# phoneline_fixer_v2_0.net
KiCad netlist of a schematic drawn in EAGLE
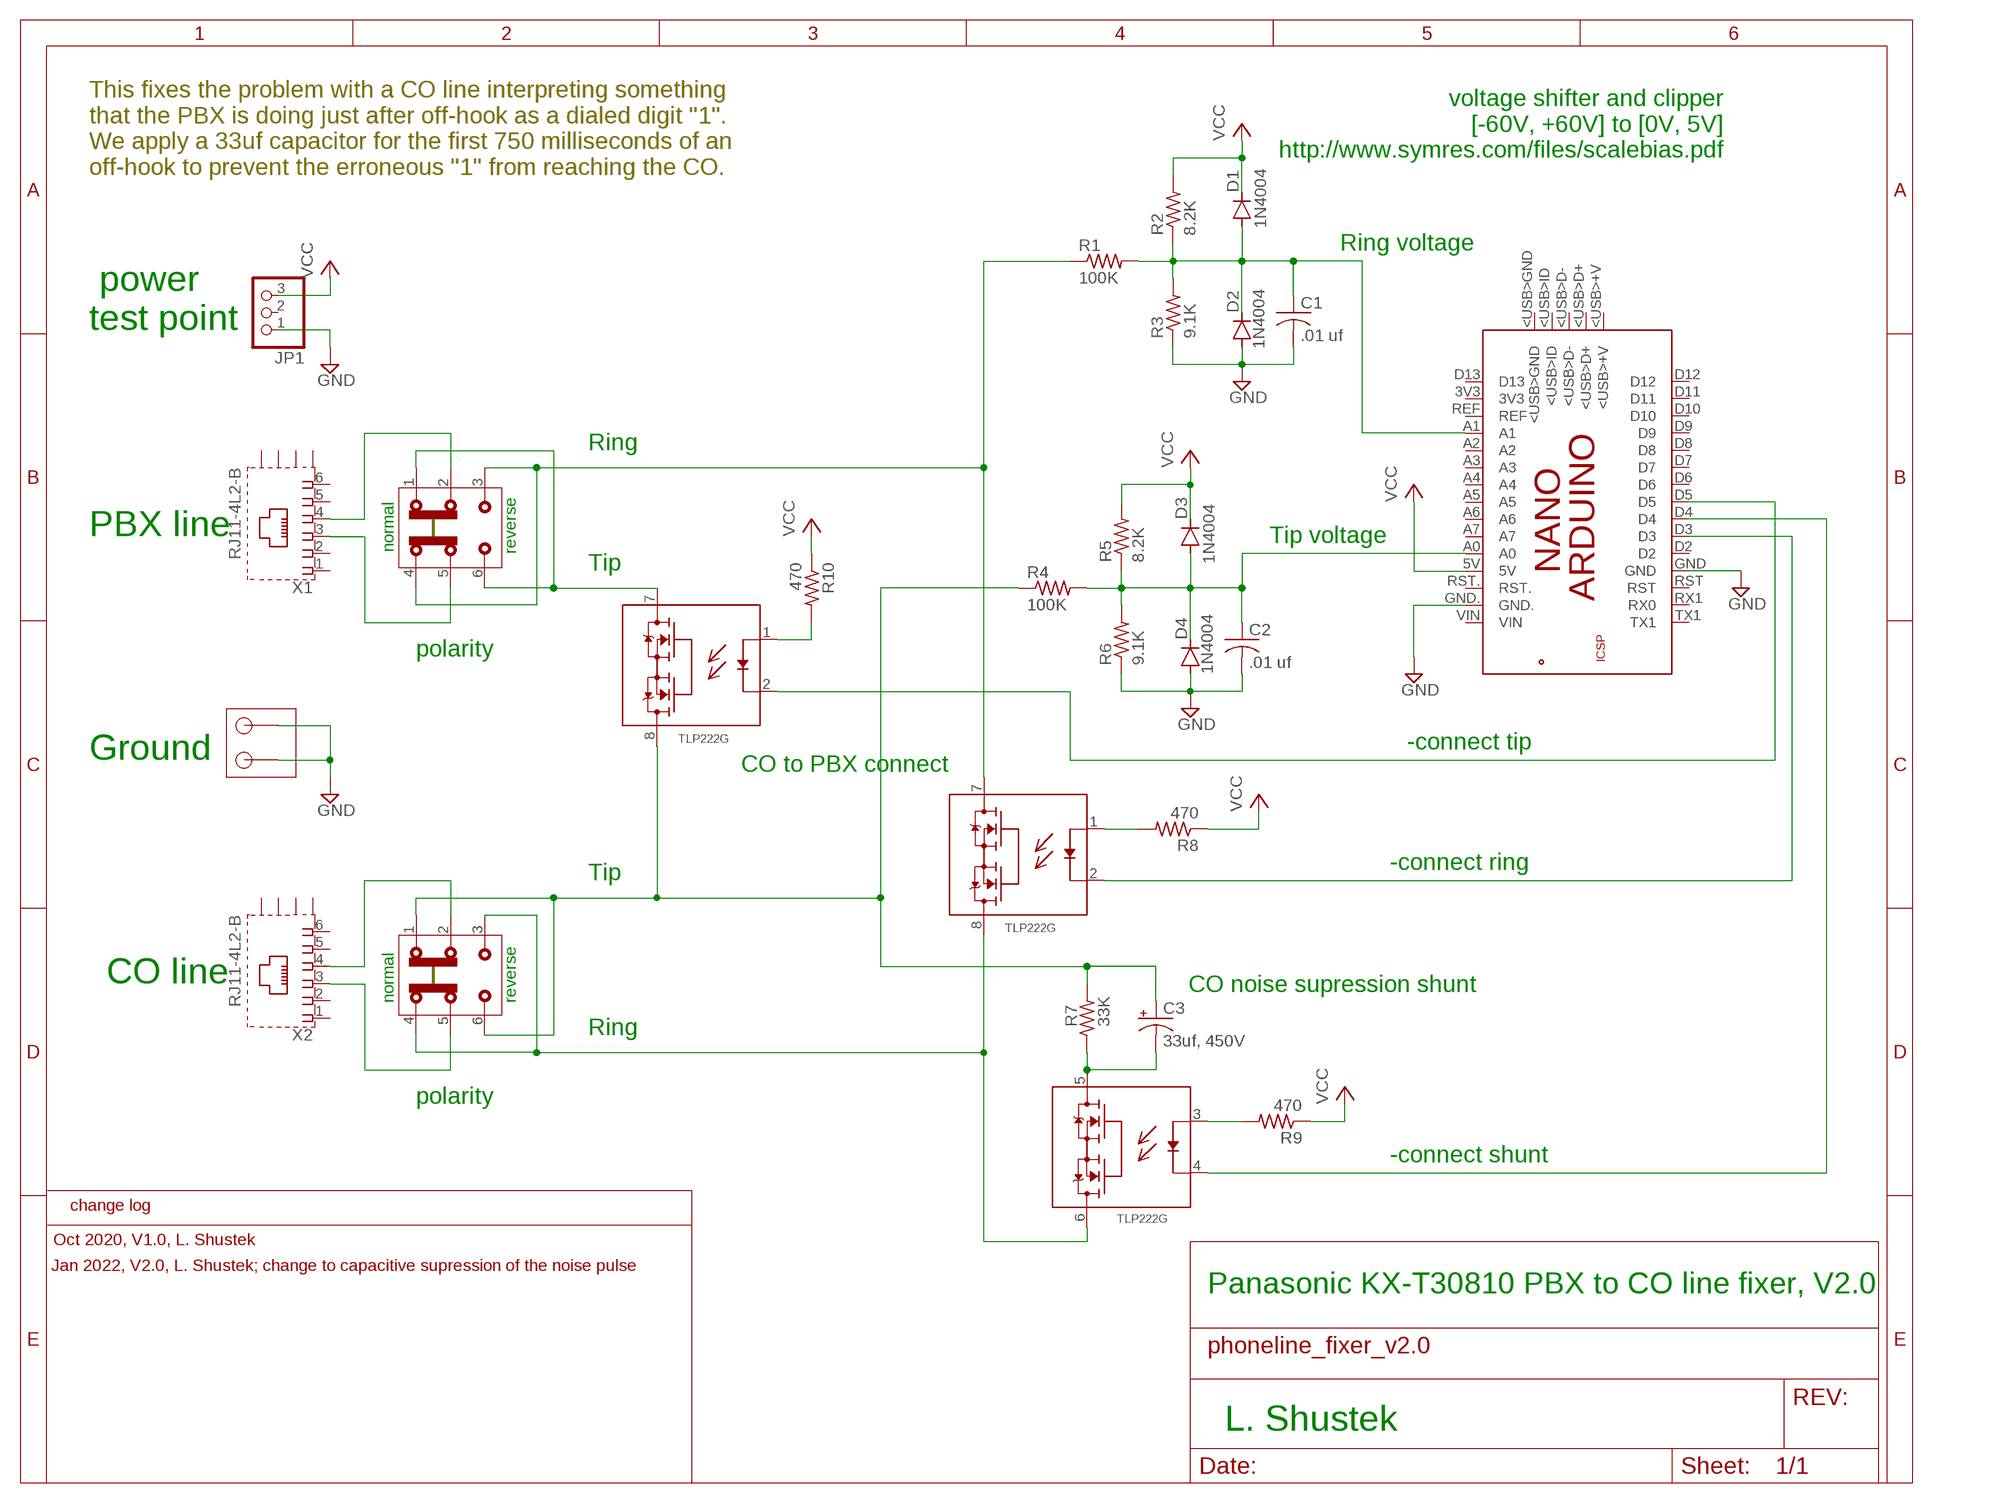
[diagram p0: schematic, sheet 1]

(export (version "E")
  (design (tool "Eeschema 10.0.6"))
  (components
    (comp (ref "C1")
      (value ".01 uf")
      (footprint "eagle-import:C050-025X075")
      (libsource (lib "eagle-import") (part "C-US050-025X075"))
    )
    (comp (ref "C2")
      (value ".01 uf")
      (footprint "eagle-import:C050-025X075")
      (libsource (lib "eagle-import") (part "C-US050-025X075"))
    )
    (comp (ref "C3")
      (value "33uf, 450V")
      (footprint "eagle-import:E7,5-18")
      (libsource (lib "eagle-import") (part "CPOL-USE7.5-18"))
    )
    (comp (ref "D1")
      (value "1N4004")
      (footprint "eagle-import:DO41-10")
      (libsource (lib "eagle-import") (part "1N4004"))
    )
    (comp (ref "D2")
      (value "1N4004")
      (footprint "eagle-import:DO41-10")
      (libsource (lib "eagle-import") (part "1N4004"))
    )
    (comp (ref "D3")
      (value "1N4004")
      (footprint "eagle-import:DO41-10")
      (libsource (lib "eagle-import") (part "1N4004"))
    )
    (comp (ref "D4")
      (value "1N4004")
      (footprint "eagle-import:DO41-10")
      (libsource (lib "eagle-import") (part "1N4004"))
    )
    (comp (ref "JP1")
      (value "PINHD-1X3")
      (footprint "eagle-import:1X03")
      (libsource (lib "eagle-import") (part "PINHD-1X3"))
    )
    (comp (ref "PCB1")
      (value "ARDUINO_NANO")
      (footprint "eagle-import:ARDUINO_NANO")
      (libsource (lib "eagle-import") (part "ARDUINO_NANO"))
    )
    (comp (ref "R1")
      (value "100K")
      (footprint "eagle-import:0207_12")
      (libsource (lib "eagle-import") (part "R-US_0207/12"))
    )
    (comp (ref "R2")
      (value "8.2K")
      (footprint "eagle-import:0207_12")
      (libsource (lib "eagle-import") (part "R-US_0207/12"))
    )
    (comp (ref "R3")
      (value "9.1K")
      (footprint "eagle-import:0207_12")
      (libsource (lib "eagle-import") (part "R-US_0207/12"))
    )
    (comp (ref "R4")
      (value "100K")
      (footprint "eagle-import:0207_12")
      (libsource (lib "eagle-import") (part "R-US_0207/12"))
    )
    (comp (ref "R5")
      (value "8.2K")
      (footprint "eagle-import:0207_12")
      (libsource (lib "eagle-import") (part "R-US_0207/12"))
    )
    (comp (ref "R6")
      (value "9.1K")
      (footprint "eagle-import:0207_12")
      (libsource (lib "eagle-import") (part "R-US_0207/12"))
    )
    (comp (ref "R7")
      (value "33K")
      (footprint "eagle-import:0414_15")
      (libsource (lib "eagle-import") (part "R-US_0414/15"))
    )
    (comp (ref "R8")
      (value "470")
      (footprint "eagle-import:0207_12")
      (libsource (lib "eagle-import") (part "R-US_0207/12"))
    )
    (comp (ref "R9")
      (value "470")
      (footprint "eagle-import:0207_12")
      (libsource (lib "eagle-import") (part "R-US_0207/12"))
    )
    (comp (ref "R10")
      (value "470")
      (footprint "eagle-import:0207_12")
      (libsource (lib "eagle-import") (part "R-US_0207/12"))
    )
    (comp (ref "U$1")
      (value "TLP222G")
      (footprint "eagle-import:DIL08")
      (libsource (lib "eagle-import") (part "PHOTORELAY"))
    )
    (comp (ref "U$2")
      (value "CONNECTOR-2PINTHIN")
      (footprint "eagle-import:CONNECTOR-2PIN-5MM_THIN")
      (libsource (lib "eagle-import") (part "CONNECTOR-2PINTHIN"))
    )
    (comp (ref "U$3")
      (value "SWITCH_SLIDE_DPDT")
      (footprint "eagle-import:SWITCH_SLIDE_DPDT")
      (libsource (lib "eagle-import") (part "SWITCH_SLIDE_DPDT"))
    )
    (comp (ref "U$4")
      (value "SWITCH_SLIDE_DPDT")
      (footprint "eagle-import:SWITCH_SLIDE_DPDT")
      (libsource (lib "eagle-import") (part "SWITCH_SLIDE_DPDT"))
    )
    (comp (ref "U$5")
      (value "TLP222G")
      (footprint "eagle-import:DIL08")
      (libsource (lib "eagle-import") (part "PHOTORELAY"))
    )
    (comp (ref "X1")
      (value "RJ11-4L2-B")
      (footprint "eagle-import:RJ11-SHIELD2")
      (fields (field (name "MF") "TYCO ELECTRONICS"))
      (libsource (lib "eagle-import") (part "RJ112-B-4L"))
    )
    (comp (ref "X2")
      (value "RJ11-4L2-B")
      (footprint "eagle-import:RJ11-SHIELD2")
      (fields (field (name "MF") "TYCO ELECTRONICS"))
      (libsource (lib "eagle-import") (part "RJ112-B-4L"))
    )
  )
  (nets
    (net (code "1") (name "GND") (class "Default")
      (node (ref "C1") (pin "2") (pinfunction "2_2") (pintype "passive"))
      (node (ref "C2") (pin "2") (pinfunction "2_2") (pintype "passive"))
      (node (ref "D2") (pin "A") (pinfunction "A_A") (pintype "passive"))
      (node (ref "D4") (pin "A") (pinfunction "A_A") (pintype "passive"))
      (node (ref "JP1") (pin "1") (pinfunction "1_1") (pintype "passive"))
      (node (ref "PCB1") (pin "GND") (pinfunction "GND_GND") (pintype "bidirectional"))
      (node (ref "PCB1") (pin "GND.") (pinfunction "GND._GND.") (pintype "bidirectional"))
      (node (ref "R3") (pin "1") (pinfunction "1_1") (pintype "passive"))
      (node (ref "R6") (pin "1") (pinfunction "1_1") (pintype "passive"))
      (node (ref "U$2") (pin "P$1") (pinfunction "P$1_P$1") (pintype "bidirectional"))
      (node (ref "U$2") (pin "P$2") (pinfunction "P$2_P$2") (pintype "bidirectional"))
    )
    (net (code "2") (name "Net-(C1-Pad1)") (class "Default")
      (node (ref "C1") (pin "1") (pinfunction "1_1") (pintype "passive"))
      (node (ref "D1") (pin "A") (pinfunction "A_A") (pintype "passive"))
      (node (ref "D2") (pin "C") (pinfunction "C_C") (pintype "passive"))
      (node (ref "PCB1") (pin "A1") (pinfunction "A1_A1") (pintype "bidirectional"))
      (node (ref "R1") (pin "2") (pinfunction "2_2") (pintype "passive"))
      (node (ref "R2") (pin "1") (pinfunction "1_1") (pintype "passive"))
      (node (ref "R3") (pin "2") (pinfunction "2_2") (pintype "passive"))
    )
    (net (code "3") (name "Net-(C2-Pad1)") (class "Default")
      (node (ref "C2") (pin "1") (pinfunction "1_1") (pintype "passive"))
      (node (ref "D3") (pin "A") (pinfunction "A_A") (pintype "passive"))
      (node (ref "D4") (pin "C") (pinfunction "C_C") (pintype "passive"))
      (node (ref "PCB1") (pin "A0") (pinfunction "A0_A0") (pintype "bidirectional"))
      (node (ref "R4") (pin "2") (pinfunction "2_2") (pintype "passive"))
      (node (ref "R5") (pin "1") (pinfunction "1_1") (pintype "passive"))
      (node (ref "R6") (pin "2") (pinfunction "2_2") (pintype "passive"))
    )
    (net (code "4") (name "Net-(U$1A-A)") (class "Default")
      (node (ref "R8") (pin "2") (pinfunction "2_2") (pintype "passive"))
      (node (ref "U$1") (pin "1") (pinfunction "A_1") (pintype "bidirectional"))
    )
    (net (code "5") (name "Net-(U$1A-C)") (class "Default")
      (node (ref "PCB1") (pin "D3") (pinfunction "D3_D3") (pintype "bidirectional"))
      (node (ref "U$1") (pin "2") (pinfunction "C_2") (pintype "bidirectional"))
    )
    (net (code "6") (name "Net-(U$1A-D1)") (class "Default")
      (node (ref "U$1") (pin "6") (pinfunction "D1_6") (pintype "bidirectional"))
      (node (ref "U$1") (pin "8") (pinfunction "D1_8") (pintype "bidirectional"))
      (node (ref "U$4") (pin "3") (pinfunction "3_3") (pintype "bidirectional"))
      (node (ref "U$4") (pin "4") (pinfunction "4_4") (pintype "bidirectional"))
    )
    (net (code "7") (name "Net-(U$1A-D2)") (class "Default")
      (node (ref "R1") (pin "1") (pinfunction "1_1") (pintype "passive"))
      (node (ref "U$1") (pin "7") (pinfunction "D2_7") (pintype "bidirectional"))
      (node (ref "U$3") (pin "3") (pinfunction "3_3") (pintype "bidirectional"))
      (node (ref "U$3") (pin "4") (pinfunction "4_4") (pintype "bidirectional"))
    )
    (net (code "8") (name "Net-(U$1B-A)") (class "Default")
      (node (ref "R9") (pin "2") (pinfunction "2_2") (pintype "passive"))
      (node (ref "U$1") (pin "3") (pinfunction "A_3") (pintype "bidirectional"))
    )
    (net (code "9") (name "Net-(U$1B-C)") (class "Default")
      (node (ref "PCB1") (pin "D4") (pinfunction "D4_D4") (pintype "bidirectional"))
      (node (ref "U$1") (pin "4") (pinfunction "C_4") (pintype "bidirectional"))
    )
    (net (code "10") (name "Net-(U$1B-D2)") (class "Default")
      (node (ref "C3") (pin "-") (pinfunction "-_-") (pintype "passive"))
      (node (ref "R7") (pin "1") (pinfunction "1_1") (pintype "passive"))
      (node (ref "U$1") (pin "5") (pinfunction "D2_5") (pintype "bidirectional"))
    )
    (net (code "11") (name "Net-(U$3-Pad2)") (class "Default")
      (node (ref "U$3") (pin "2") (pinfunction "2_2") (pintype "bidirectional"))
      (node (ref "X1") (pin "4") (pinfunction "4_4") (pintype "passive"))
    )
    (net (code "12") (name "Net-(U$3-Pad5)") (class "Default")
      (node (ref "U$3") (pin "5") (pinfunction "5_5") (pintype "bidirectional"))
      (node (ref "X1") (pin "3") (pinfunction "3_3") (pintype "passive"))
    )
    (net (code "13") (name "Net-(U$4-Pad2)") (class "Default")
      (node (ref "U$4") (pin "2") (pinfunction "2_2") (pintype "bidirectional"))
      (node (ref "X2") (pin "4") (pinfunction "4_4") (pintype "passive"))
    )
    (net (code "14") (name "Net-(U$4-Pad5)") (class "Default")
      (node (ref "U$4") (pin "5") (pinfunction "5_5") (pintype "bidirectional"))
      (node (ref "X2") (pin "3") (pinfunction "3_3") (pintype "passive"))
    )
    (net (code "15") (name "Net-(U$5A-A)") (class "Default")
      (node (ref "R10") (pin "2") (pinfunction "2_2") (pintype "passive"))
      (node (ref "U$5") (pin "1") (pinfunction "A_1") (pintype "bidirectional"))
    )
    (net (code "16") (name "Net-(U$5A-C)") (class "Default")
      (node (ref "PCB1") (pin "D5") (pinfunction "D5_D5") (pintype "bidirectional"))
      (node (ref "U$5") (pin "2") (pinfunction "C_2") (pintype "bidirectional"))
    )
    (net (code "17") (name "Net-(U$5A-D1)") (class "Default")
      (node (ref "C3") (pin "+") (pinfunction "+_+") (pintype "passive"))
      (node (ref "R4") (pin "1") (pinfunction "1_1") (pintype "passive"))
      (node (ref "R7") (pin "2") (pinfunction "2_2") (pintype "passive"))
      (node (ref "U$4") (pin "1") (pinfunction "1_1") (pintype "bidirectional"))
      (node (ref "U$4") (pin "6") (pinfunction "6_6") (pintype "bidirectional"))
      (node (ref "U$5") (pin "8") (pinfunction "D1_8") (pintype "bidirectional"))
    )
    (net (code "18") (name "Net-(U$5A-D2)") (class "Default")
      (node (ref "U$3") (pin "1") (pinfunction "1_1") (pintype "bidirectional"))
      (node (ref "U$3") (pin "6") (pinfunction "6_6") (pintype "bidirectional"))
      (node (ref "U$5") (pin "7") (pinfunction "D2_7") (pintype "bidirectional"))
    )
    (net (code "19") (name "VCC") (class "Default")
      (node (ref "D1") (pin "C") (pinfunction "C_C") (pintype "passive"))
      (node (ref "D3") (pin "C") (pinfunction "C_C") (pintype "passive"))
      (node (ref "JP1") (pin "3") (pinfunction "3_3") (pintype "passive"))
      (node (ref "PCB1") (pin "5V") (pinfunction "5V_5V") (pintype "bidirectional"))
      (node (ref "R10") (pin "1") (pinfunction "1_1") (pintype "passive"))
      (node (ref "R2") (pin "2") (pinfunction "2_2") (pintype "passive"))
      (node (ref "R5") (pin "2") (pinfunction "2_2") (pintype "passive"))
      (node (ref "R8") (pin "1") (pinfunction "1_1") (pintype "passive"))
      (node (ref "R9") (pin "1") (pinfunction "1_1") (pintype "passive"))
    )
    (net (code "20") (name "unconnected-(JP1-Pad2)") (class "Default")
      (node (ref "JP1") (pin "2") (pinfunction "2_2") (pintype "passive"))
    )
    (net (code "21") (name "unconnected-(PCB1-Pad3V3)") (class "Default")
      (node (ref "PCB1") (pin "3V3") (pinfunction "3V3_3V3") (pintype "bidirectional"))
    )
    (net (code "22") (name "unconnected-(PCB1-Pad5V.)") (class "Default")
      (node (ref "PCB1") (pin "5V.") (pinfunction "5V._5V.") (pintype "bidirectional"))
    )
    (net (code "23") (name "unconnected-(PCB1-Pad<USB>+V)") (class "Default")
      (node (ref "PCB1") (pin "<USB>+V") (pinfunction "<USB>+V_<USB>+V") (pintype "bidirectional"))
    )
    (net (code "24") (name "unconnected-(PCB1-Pad<USB>D+)") (class "Default")
      (node (ref "PCB1") (pin "<USB>D+") (pinfunction "<USB>D+_<USB>D+") (pintype "bidirectional"))
    )
    (net (code "25") (name "unconnected-(PCB1-Pad<USB>D-)") (class "Default")
      (node (ref "PCB1") (pin "<USB>D-") (pinfunction "<USB>D-_<USB>D-") (pintype "bidirectional"))
    )
    (net (code "26") (name "unconnected-(PCB1-Pad<USB>GND)") (class "Default")
      (node (ref "PCB1") (pin "<USB>GND") (pinfunction "<USB>GND_<USB>GND") (pintype "bidirectional"))
    )
    (net (code "27") (name "unconnected-(PCB1-Pad<USB>ID)") (class "Default")
      (node (ref "PCB1") (pin "<USB>ID") (pinfunction "<USB>ID_<USB>ID") (pintype "bidirectional"))
    )
    (net (code "28") (name "unconnected-(PCB1-PadA2)") (class "Default")
      (node (ref "PCB1") (pin "A2") (pinfunction "A2_A2") (pintype "bidirectional"))
    )
    (net (code "29") (name "unconnected-(PCB1-PadA3)") (class "Default")
      (node (ref "PCB1") (pin "A3") (pinfunction "A3_A3") (pintype "bidirectional"))
    )
    (net (code "30") (name "unconnected-(PCB1-PadA4)") (class "Default")
      (node (ref "PCB1") (pin "A4") (pinfunction "A4_A4") (pintype "bidirectional"))
    )
    (net (code "31") (name "unconnected-(PCB1-PadA5)") (class "Default")
      (node (ref "PCB1") (pin "A5") (pinfunction "A5_A5") (pintype "bidirectional"))
    )
    (net (code "32") (name "unconnected-(PCB1-PadA6)") (class "Default")
      (node (ref "PCB1") (pin "A6") (pinfunction "A6_A6") (pintype "bidirectional"))
    )
    (net (code "33") (name "unconnected-(PCB1-PadA7)") (class "Default")
      (node (ref "PCB1") (pin "A7") (pinfunction "A7_A7") (pintype "bidirectional"))
    )
    (net (code "34") (name "unconnected-(PCB1-PadD2)") (class "Default")
      (node (ref "PCB1") (pin "D2") (pinfunction "D2_D2") (pintype "bidirectional"))
    )
    (net (code "35") (name "unconnected-(PCB1-PadD6)") (class "Default")
      (node (ref "PCB1") (pin "D6") (pinfunction "D6_D6") (pintype "bidirectional"))
    )
    (net (code "36") (name "unconnected-(PCB1-PadD7)") (class "Default")
      (node (ref "PCB1") (pin "D7") (pinfunction "D7_D7") (pintype "bidirectional"))
    )
    (net (code "37") (name "unconnected-(PCB1-PadD8)") (class "Default")
      (node (ref "PCB1") (pin "D8") (pinfunction "D8_D8") (pintype "bidirectional"))
    )
    (net (code "38") (name "unconnected-(PCB1-PadD9)") (class "Default")
      (node (ref "PCB1") (pin "D9") (pinfunction "D9_D9") (pintype "bidirectional"))
    )
    (net (code "39") (name "unconnected-(PCB1-PadD10)") (class "Default")
      (node (ref "PCB1") (pin "D10") (pinfunction "D10_D10") (pintype "bidirectional"))
    )
    (net (code "40") (name "unconnected-(PCB1-PadD11)") (class "Default")
      (node (ref "PCB1") (pin "D11") (pinfunction "D11_D11") (pintype "bidirectional"))
    )
    (net (code "41") (name "unconnected-(PCB1-PadD12)") (class "Default")
      (node (ref "PCB1") (pin "D12") (pinfunction "D12_D12") (pintype "bidirectional"))
    )
    (net (code "42") (name "unconnected-(PCB1-PadD13)") (class "Default")
      (node (ref "PCB1") (pin "D13") (pinfunction "D13_D13") (pintype "bidirectional"))
    )
    (net (code "43") (name "unconnected-(PCB1-PadGND_)") (class "Default")
      (node (ref "PCB1") (pin "GND_") (pinfunction "GND__GND_") (pintype "bidirectional"))
    )
    (net (code "44") (name "unconnected-(PCB1-PadMISO)") (class "Default")
      (node (ref "PCB1") (pin "MISO") (pinfunction "MISO_MISO") (pintype "bidirectional"))
    )
    (net (code "45") (name "unconnected-(PCB1-PadMOSI)") (class "Default")
      (node (ref "PCB1") (pin "MOSI") (pinfunction "MOSI_MOSI") (pintype "bidirectional"))
    )
    (net (code "46") (name "unconnected-(PCB1-PadREF)") (class "Default")
      (node (ref "PCB1") (pin "REF") (pinfunction "REF_REF") (pintype "bidirectional"))
    )
    (net (code "47") (name "unconnected-(PCB1-PadRESET..)") (class "Default")
      (node (ref "PCB1") (pin "RESET..") (pinfunction "RESET.._RESET..") (pintype "bidirectional"))
    )
    (net (code "48") (name "unconnected-(PCB1-PadRST)") (class "Default")
      (node (ref "PCB1") (pin "RST") (pinfunction "RST_RST") (pintype "bidirectional"))
    )
    (net (code "49") (name "unconnected-(PCB1-PadRST.)") (class "Default")
      (node (ref "PCB1") (pin "RST.") (pinfunction "RST._RST.") (pintype "bidirectional"))
    )
    (net (code "50") (name "unconnected-(PCB1-PadSCK)") (class "Default")
      (node (ref "PCB1") (pin "SCK") (pinfunction "SCK_SCK") (pintype "bidirectional"))
    )
    (net (code "51") (name "unconnected-(PCB1-PadTX1)") (class "Default")
      (node (ref "PCB1") (pin "TX1") (pinfunction "TX1_TX1") (pintype "bidirectional"))
    )
    (net (code "52") (name "unconnected-(PCB1-PadVIN)") (class "Default")
      (node (ref "PCB1") (pin "VIN") (pinfunction "VIN_VIN") (pintype "bidirectional"))
    )
    (net (code "53") (name "unconnected-(PCB1-RX0-PadRX1)") (class "Default")
      (node (ref "PCB1") (pin "RX1") (pinfunction "RX0_RX1") (pintype "bidirectional"))
    )
    (net (code "54") (name "unconnected-(X1-Pad1)") (class "Default")
      (node (ref "X1") (pin "1") (pinfunction "1_1") (pintype "passive"))
    )
    (net (code "55") (name "unconnected-(X1-Pad2)") (class "Default")
      (node (ref "X1") (pin "2") (pinfunction "2_2") (pintype "passive"))
    )
    (net (code "56") (name "unconnected-(X1-Pad5)") (class "Default")
      (node (ref "X1") (pin "5") (pinfunction "5_5") (pintype "passive"))
    )
    (net (code "57") (name "unconnected-(X1-Pad6)") (class "Default")
      (node (ref "X1") (pin "6") (pinfunction "6_6") (pintype "passive"))
    )
    (net (code "58") (name "unconnected-(X1-S-PadS1)") (class "Default")
      (node (ref "X1") (pin "S1") (pinfunction "S_S1") (pintype "passive"))
    )
    (net (code "59") (name "unconnected-(X1-S-PadS2)") (class "Default")
      (node (ref "X1") (pin "S2") (pinfunction "S_S2") (pintype "passive"))
    )
    (net (code "60") (name "unconnected-(X1-S-PadS3)") (class "Default")
      (node (ref "X1") (pin "S3") (pinfunction "S_S3") (pintype "passive"))
    )
    (net (code "61") (name "unconnected-(X1-S-PadS4)") (class "Default")
      (node (ref "X1") (pin "S4") (pinfunction "S_S4") (pintype "passive"))
    )
    (net (code "62") (name "unconnected-(X2-Pad1)") (class "Default")
      (node (ref "X2") (pin "1") (pinfunction "1_1") (pintype "passive"))
    )
    (net (code "63") (name "unconnected-(X2-Pad2)") (class "Default")
      (node (ref "X2") (pin "2") (pinfunction "2_2") (pintype "passive"))
    )
    (net (code "64") (name "unconnected-(X2-Pad5)") (class "Default")
      (node (ref "X2") (pin "5") (pinfunction "5_5") (pintype "passive"))
    )
    (net (code "65") (name "unconnected-(X2-Pad6)") (class "Default")
      (node (ref "X2") (pin "6") (pinfunction "6_6") (pintype "passive"))
    )
    (net (code "66") (name "unconnected-(X2-S-PadS1)") (class "Default")
      (node (ref "X2") (pin "S1") (pinfunction "S_S1") (pintype "passive"))
    )
    (net (code "67") (name "unconnected-(X2-S-PadS2)") (class "Default")
      (node (ref "X2") (pin "S2") (pinfunction "S_S2") (pintype "passive"))
    )
    (net (code "68") (name "unconnected-(X2-S-PadS3)") (class "Default")
      (node (ref "X2") (pin "S3") (pinfunction "S_S3") (pintype "passive"))
    )
    (net (code "69") (name "unconnected-(X2-S-PadS4)") (class "Default")
      (node (ref "X2") (pin "S4") (pinfunction "S_S4") (pintype "passive"))
    )
  )
)
